# sd-card.net
KiCad netlist of a schematic drawn in Altium Designer
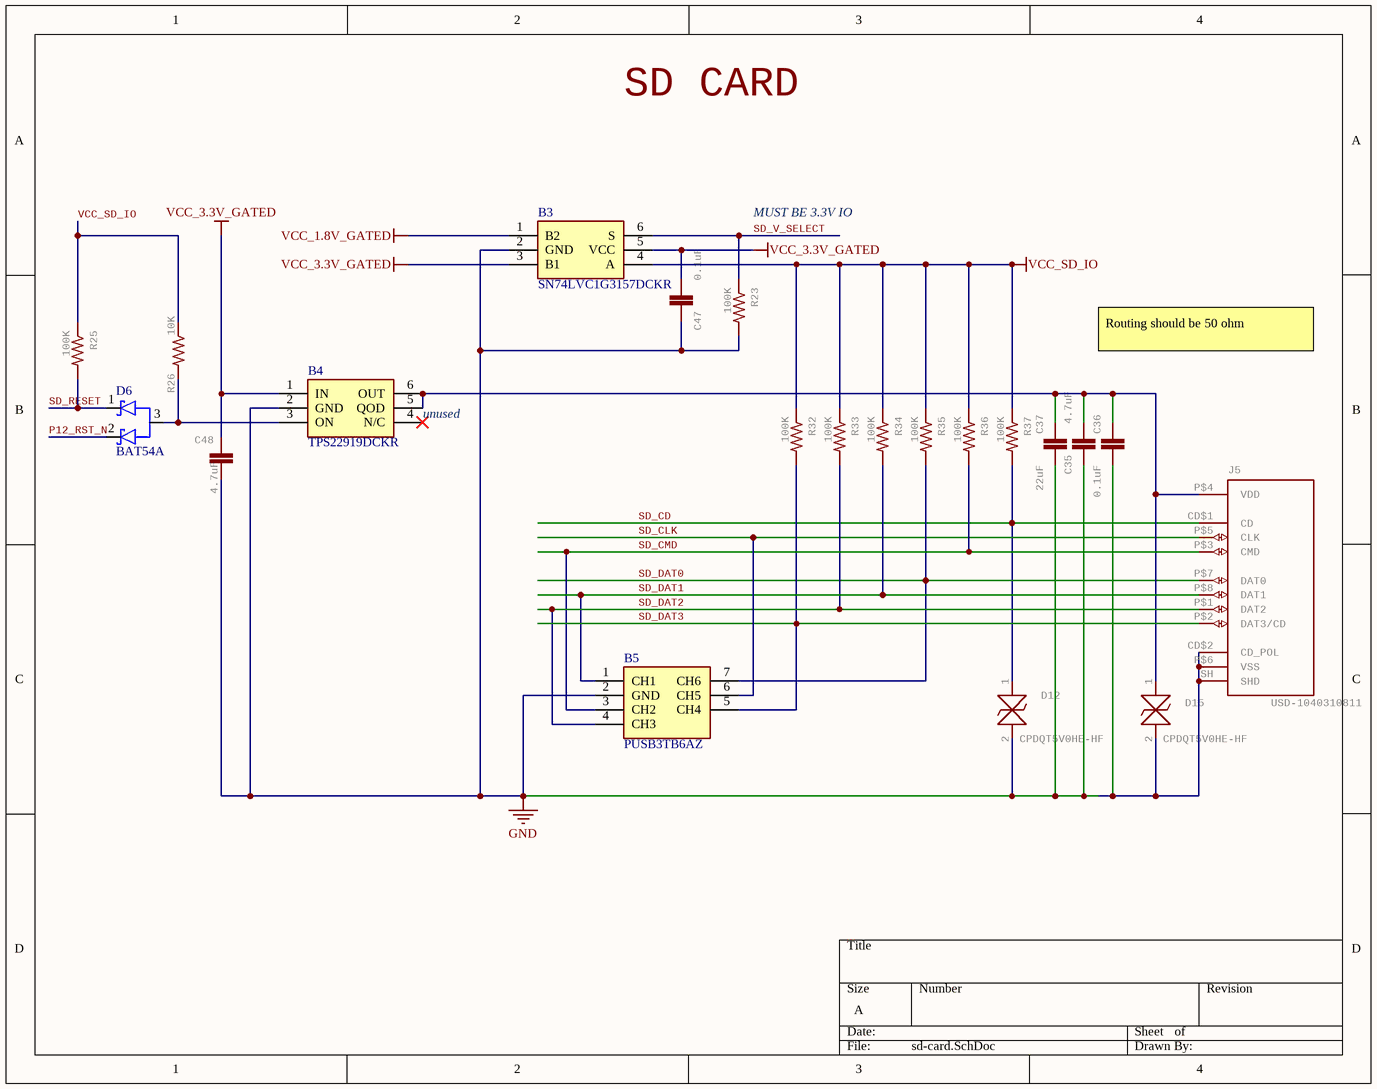
[diagram p0: sd-card.SchDoc]

(export (version "E")
  (design (tool "Eeschema 10.0.6"))
  (components
    (comp (ref "B3")
      (value "SN74LVC1G3157DCKR")
      (footprint "SOT65P210X110-6N")
      (description "SN74LVC1G3157DCKR, Analogue Switch Single SPDT, 3, 5V, 6-Pin, SC-70")
      (fields (field (name "MOUSER PART NUMBER") "595-SN74LVC1G3157DCK"))
      (libsource (lib "SN74LVC1G3157DCKR") (part "SN74LVC1G3157DCKR"))
    )
    (comp (ref "B4")
      (value "TPS22919DCKR")
      (footprint "SOT65P210X110-6N")
      (description "5.5V, 1.5A, 90m self-protected load switch with controlled rise time")
      (fields (field (name "MOUSER PART NUMBER") "595-TPS22919DCKR"))
      (libsource (lib "TPS22919DCKR") (part "TPS22919DCKR"))
    )
    (comp (ref "B5")
      (value "PUSB3TB6AZ")
      (footprint "PUSB3TB6AZ")
      (description "NEXPERIA - PUSB3TB6AZ - DIODE, ESD PROTECTION, 5.5V, 0.27PF")
      (fields (field (name "MOUSER PART NUMBER") "771-PUSB3TB6AZ"))
      (libsource (lib "PUSB3TB6AZ") (part "PUSB3TB6AZ"))
    )
    (comp (ref "C35")
      (value "4.7uF")
      (footprint "0402-CAP")
      (description "CapacitorStandard 0603 ceramic capacitor, and 0.1\" leaded capacitor.")
      (fields (field (name "MPN") "JMK105BBJ475MV-F"))
      (libsource (lib "rt10") (part "CAP0402-CAP"))
    )
    (comp (ref "C36")
      (value "0.1uF")
      (footprint "0402-CAP")
      (description "CAPACITOR, European symbol")
      (fields (field (name "MPN") "C0402C104Z4VAC"))
      (libsource (lib "rt10") (part "C-EUC0201"))
    )
    (comp (ref "C37")
      (value "22uF")
      (footprint "0805")
      (fields (field (name "MPN") "CL21A226MQQNNNE"))
      (libsource (lib "rt10") (part "22UF-0805-6.3V-20%"))
    )
    (comp (ref "C47")
      (value "0.1uF")
      (footprint "0402-CAP")
      (description "CAPACITOR, European symbol")
      (fields (field (name "MPN") "C0402C104Z4VAC"))
      (libsource (lib "") (part "C-EUC0201_1"))
    )
    (comp (ref "C48")
      (value "4.7uF")
      (footprint "0402-CAP")
      (description "CapacitorStandard 0603 ceramic capacitor, and 0.1\" leaded capacitor.")
      (fields (field (name "MPN") "JMK105BBJ475MV-F"))
      (libsource (lib "openmv-ae3") (part "CAP0402-CAP"))
    )
    (comp (ref "D6")
      (value "BAT54A")
      (footprint "SOT65P210X110-3N")
      (description "Diode Array 1 Pair Common Anode Schottky 30V 200mA (DC) Surface Mount SC-70, SOT-323")
      (fields (field (name "PART NUMBER") "BAT54AW,115"))
      (libsource (lib "stm32n657") (part "BAT54AW-7-F"))
    )
    (comp (ref "D12")
      (value "CPDQT5V0HE-HF")
      (footprint "CPDQT5V0HEHF")
      (description "ESD Suppressors / TVS Diodes DIODE ESD 5VWM 65W 0402/SOD-923F   Source:  Datasheet")
      (fields (field (name "MOUSER_PART_NUMBER") "MOUSER_PART_NUMBER"))
      (libsource (lib "openmv-ae3") (part "CPDQT5V0HE-HF"))
    )
    (comp (ref "D15")
      (value "CPDQT5V0HE-HF")
      (footprint "CPDQT5V0HEHF")
      (description "ESD Suppressors / TVS Diodes DIODE ESD 5VWM 65W 0402/SOD-923F   Source:  Datasheet")
      (fields (field (name "MOUSER_PART_NUMBER") "MOUSER_PART_NUMBER"))
      (libsource (lib "openmv-ae3") (part "CPDQT5V0HE-HF"))
    )
    (comp (ref "J5")
      (value "USD-1040310811")
      (footprint "1040310811")
      (description "uSD Slot")
      (fields (field (name "MPN") "104031-0811"))
      (libsource (lib "rt10") (part "USD-1040310811"))
    )
    (comp (ref "R23")
      (value "100K")
      (footprint "0402-RES")
      (description "ResistorBasic schematic elements and footprints for 0603, 1206, and PTH resistors.")
      (fields (field (name "MPN") "AC0402FR-07100KL"))
      (libsource (lib "rt10") (part "RESISTOR0402-RES"))
    )
    (comp (ref "R25")
      (value "100K")
      (footprint "0402-RES")
      (description "ResistorBasic schematic elements and footprints for 0603, 1206, and PTH resistors.")
      (fields (field (name "MPN") "AC0402FR-07100KL"))
      (libsource (lib "rt10") (part "RESISTOR0402-RES"))
    )
    (comp (ref "R26")
      (value "10K")
      (footprint "0402-RES")
      (description "ResistorBasic schematic elements and footprints for 0603, 1206, and PTH resistors.")
      (fields (field (name "MPN") "AC0402FR-1310K"))
      (libsource (lib "rt10") (part "RESISTOR0402-RES"))
    )
    (comp (ref "R32")
      (value "100K")
      (footprint "0402-RES")
      (description "ResistorBasic schematic elements and footprints for 0603, 1206, and PTH resistors.")
      (fields (field (name "MPN") "AC0402FR-07100KL"))
      (libsource (lib "rt10") (part "RESISTOR0402-RES"))
    )
    (comp (ref "R33")
      (value "100K")
      (footprint "0402-RES")
      (description "ResistorBasic schematic elements and footprints for 0603, 1206, and PTH resistors.")
      (fields (field (name "MPN") "AC0402FR-07100KL"))
      (libsource (lib "rt10") (part "RESISTOR0402-RES"))
    )
    (comp (ref "R34")
      (value "100K")
      (footprint "0402-RES")
      (description "ResistorBasic schematic elements and footprints for 0603, 1206, and PTH resistors.")
      (fields (field (name "MPN") "AC0402FR-07100KL"))
      (libsource (lib "rt10") (part "RESISTOR0402-RES"))
    )
    (comp (ref "R35")
      (value "100K")
      (footprint "0402-RES")
      (description "ResistorBasic schematic elements and footprints for 0603, 1206, and PTH resistors.")
      (fields (field (name "MPN") "AC0402FR-07100KL"))
      (libsource (lib "rt10") (part "RESISTOR0402-RES"))
    )
    (comp (ref "R36")
      (value "100K")
      (footprint "0402-RES")
      (description "ResistorBasic schematic elements and footprints for 0603, 1206, and PTH resistors.")
      (fields (field (name "MPN") "AC0402FR-07100KL"))
      (libsource (lib "rt10") (part "RESISTOR0402-RES"))
    )
    (comp (ref "R37")
      (value "100K")
      (footprint "0402-RES")
      (description "ResistorBasic schematic elements and footprints for 0603, 1206, and PTH resistors.")
      (fields (field (name "MPN") "AC0402FR-07100KL"))
      (libsource (lib "rt10") (part "RESISTOR0402-RES"))
    )
  )
  (nets
    (net (code "1") (name "/P12_RST_N") (class "Default")
      (node (ref "D6") (pin "2") (pinfunction "C2_2") (pintype "passive"))
    )
    (net (code "2") (name "/SD_CD") (class "Default")
      (node (ref "D12") (pin "1") (pinfunction "1_1") (pintype "bidirectional"))
      (node (ref "J5") (pin "CD$1") (pinfunction "CD_CD$1") (pintype "power_in"))
      (node (ref "R37") (pin "2") (pinfunction "2_2") (pintype "passive"))
    )
    (net (code "3") (name "/SD_CLK") (class "Default")
      (node (ref "B5") (pin "6") (pinfunction "CH5_6") (pintype "passive"))
      (node (ref "J5") (pin "P$5") (pinfunction "CLK_P$5") (pintype "bidirectional"))
    )
    (net (code "4") (name "/SD_CMD") (class "Default")
      (node (ref "B5") (pin "3") (pinfunction "CH2_3") (pintype "passive"))
      (node (ref "J5") (pin "P$3") (pinfunction "CMD_P$3") (pintype "bidirectional"))
      (node (ref "R36") (pin "2") (pinfunction "2_2") (pintype "passive"))
    )
    (net (code "5") (name "/SD_DAT0") (class "Default")
      (node (ref "B5") (pin "7") (pinfunction "CH6_7") (pintype "passive"))
      (node (ref "J5") (pin "P$7") (pinfunction "DAT0_P$7") (pintype "bidirectional"))
      (node (ref "R35") (pin "2") (pinfunction "2_2") (pintype "passive"))
    )
    (net (code "6") (name "/SD_DAT1") (class "Default")
      (node (ref "B5") (pin "1") (pinfunction "CH1_1") (pintype "passive"))
      (node (ref "J5") (pin "P$8") (pinfunction "DAT1_P$8") (pintype "bidirectional"))
      (node (ref "R34") (pin "2") (pinfunction "2_2") (pintype "passive"))
    )
    (net (code "7") (name "/SD_DAT2") (class "Default")
      (node (ref "B5") (pin "4") (pinfunction "CH3_4") (pintype "passive"))
      (node (ref "J5") (pin "P$1") (pinfunction "DAT2_P$1") (pintype "bidirectional"))
      (node (ref "R33") (pin "2") (pinfunction "2_2") (pintype "passive"))
    )
    (net (code "8") (name "/SD_DAT3") (class "Default")
      (node (ref "B5") (pin "5") (pinfunction "CH4_5") (pintype "passive"))
      (node (ref "J5") (pin "P$2") (pinfunction "DAT3/CD_P$2") (pintype "bidirectional"))
      (node (ref "R32") (pin "2") (pinfunction "2_2") (pintype "passive"))
    )
    (net (code "9") (name "/SD_RESET") (class "Default")
      (node (ref "D6") (pin "1") (pinfunction "C1_1") (pintype "passive"))
      (node (ref "R25") (pin "2") (pinfunction "2_2") (pintype "passive"))
    )
    (net (code "10") (name "/SD_V_SELECT") (class "Default")
      (node (ref "B3") (pin "6") (pinfunction "S_6") (pintype "passive"))
      (node (ref "R23") (pin "1") (pinfunction "1_1") (pintype "passive"))
    )
    (net (code "11") (name "GND") (class "Default")
      (node (ref "B3") (pin "2") (pinfunction "GND_2") (pintype "passive"))
      (node (ref "B4") (pin "2") (pinfunction "GND_2") (pintype "passive"))
      (node (ref "B5") (pin "2") (pinfunction "GND_2") (pintype "passive"))
      (node (ref "C35") (pin "1") (pinfunction "1_1") (pintype "passive"))
      (node (ref "C36") (pin "2") (pinfunction "2_2") (pintype "passive"))
      (node (ref "C37") (pin "2") (pinfunction "2_2") (pintype "passive"))
      (node (ref "C47") (pin "1") (pinfunction "1_1") (pintype "passive"))
      (node (ref "C48") (pin "2") (pinfunction "2_2") (pintype "passive"))
      (node (ref "D12") (pin "2") (pinfunction "2_2") (pintype "bidirectional"))
      (node (ref "D15") (pin "2") (pinfunction "2_2") (pintype "bidirectional"))
      (node (ref "J5") (pin "CD$2") (pinfunction "CD_POL_CD$2") (pintype "power_in"))
      (node (ref "J5") (pin "P$6") (pinfunction "VSS_P$6") (pintype "power_in"))
      (node (ref "J5") (pin "SH") (pinfunction "SHD_SH") (pintype "power_in"))
      (node (ref "R23") (pin "2") (pinfunction "2_2") (pintype "passive"))
    )
    (net (code "12") (name "Net-(B4-ON)") (class "Default")
      (node (ref "B4") (pin "3") (pinfunction "ON_3") (pintype "passive"))
      (node (ref "D6") (pin "3") (pinfunction "CA_3") (pintype "passive"))
      (node (ref "R26") (pin "2") (pinfunction "2_2") (pintype "passive"))
    )
    (net (code "13") (name "Net-(B4-OUT)") (class "Default")
      (node (ref "B4") (pin "5") (pinfunction "QOD_5") (pintype "passive"))
      (node (ref "B4") (pin "6") (pinfunction "OUT_6") (pintype "passive"))
      (node (ref "C35") (pin "2") (pinfunction "2_2") (pintype "passive"))
      (node (ref "C36") (pin "1") (pinfunction "1_1") (pintype "passive"))
      (node (ref "C37") (pin "1") (pinfunction "1_1") (pintype "passive"))
      (node (ref "D15") (pin "1") (pinfunction "1_1") (pintype "bidirectional"))
      (node (ref "J5") (pin "P$4") (pinfunction "VDD_P$4") (pintype "power_in"))
    )
    (net (code "14") (name "VCC_1.8V_GATED") (class "Default")
      (node (ref "B3") (pin "1") (pinfunction "B2_1") (pintype "passive"))
    )
    (net (code "15") (name "VCC_3.3V_GATED") (class "Default")
      (node (ref "B3") (pin "3") (pinfunction "B1_3") (pintype "passive"))
      (node (ref "B3") (pin "5") (pinfunction "VCC_5") (pintype "passive"))
      (node (ref "B4") (pin "1") (pinfunction "IN_1") (pintype "passive"))
      (node (ref "C47") (pin "2") (pinfunction "2_2") (pintype "passive"))
      (node (ref "C48") (pin "1") (pinfunction "1_1") (pintype "passive"))
    )
    (net (code "16") (name "VCC_SD_IO") (class "Default")
      (node (ref "B3") (pin "4") (pinfunction "A_4") (pintype "passive"))
      (node (ref "R25") (pin "1") (pinfunction "1_1") (pintype "passive"))
      (node (ref "R26") (pin "1") (pinfunction "1_1") (pintype "passive"))
      (node (ref "R32") (pin "1") (pinfunction "1_1") (pintype "passive"))
      (node (ref "R33") (pin "1") (pinfunction "1_1") (pintype "passive"))
      (node (ref "R34") (pin "1") (pinfunction "1_1") (pintype "passive"))
      (node (ref "R35") (pin "1") (pinfunction "1_1") (pintype "passive"))
      (node (ref "R36") (pin "1") (pinfunction "1_1") (pintype "passive"))
      (node (ref "R37") (pin "1") (pinfunction "1_1") (pintype "passive"))
    )
    (net (code "17") (name "unconnected-(B4-N{slash}C-Pad4)") (class "Default")
      (node (ref "B4") (pin "4") (pinfunction "N/C_4") (pintype "passive+no_connect"))
    )
  )
)
